# SCH.net
KiCad netlist of a schematic drawn in Altium Designer
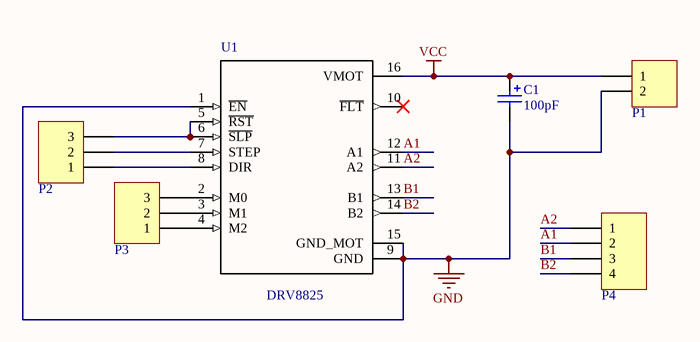
[diagram p0: SCH.SchDoc]

(export (version "E")
  (design (tool "Eeschema 10.0.6"))
  (components
    (comp (ref "C1")
      (value "100pF")
      (footprint "CP1/2")
      (description "Polarized Capacitor (Radial)")
      (fields (field (name "Comment") "Cap Pol"))
      (libsource (lib "PIF_Library") (part "Cap Pol"))
    )
    (comp (ref "P1")
      (value "Domino 2")
      (footprint "DOMINO 2- 5mm")
      (description "Domino, 2-Pin")
      (fields (field (name "PUBLISHER") "Altium Limited"))
      (libsource (lib "PIF_Library") (part "Domino 2"))
    )
    (comp (ref "P2")
      (value "Header 3")
      (footprint "JP3")
      (description "Header, 3-Pin")
      (fields (field (name "PUBLISHER") "Altium Limited"))
      (libsource (lib "PIF_Library") (part "Header 3"))
    )
    (comp (ref "P3")
      (value "Header 3")
      (footprint "JP3")
      (description "Header, 3-Pin")
      (fields (field (name "PUBLISHER") "Altium Limited"))
      (libsource (lib "PIF_Library") (part "Header 3"))
    )
    (comp (ref "P4")
      (value "Header 4")
      (footprint "JP4")
      (description "Header, 4-Pin")
      (fields (field (name "PUBLISHER") "Altium Limited"))
      (libsource (lib "PIF_Library") (part "Header 4"))
    )
    (comp (ref "U1")
      (value "DRV8825")
      (footprint "*IC_DRV8825_STEPPER_MOTOR_DRIVER_CARRIER")
      (description "DRV8825 Motor Controller/Driver Power Management Evaluation Board")
      (fields (field (name "MP") "DRV8825 STEPPER MOTOR DRIVER CARRIER") (field (name "MF") "Pololu"))
      (libsource (lib "DRV8825_STEPPER_MOTOR_DRIVER_CARRIER") (part "DRV8825_STEPPER_MOTOR_DRIVER_CARRIER"))
    )
  )
  (nets
    (net (code "1") (name "/A1") (class "Default")
      (node (ref "P4") (pin "2") (pinfunction "2_2") (pintype "passive"))
      (node (ref "U1") (pin "12") (pinfunction "A1_12") (pintype "output"))
    )
    (net (code "2") (name "/A2") (class "Default")
      (node (ref "P4") (pin "1") (pinfunction "1_1") (pintype "passive"))
      (node (ref "U1") (pin "11") (pinfunction "A2_11") (pintype "output"))
    )
    (net (code "3") (name "/B1") (class "Default")
      (node (ref "P4") (pin "3") (pinfunction "3_3") (pintype "passive"))
      (node (ref "U1") (pin "13") (pinfunction "B1_13") (pintype "output"))
    )
    (net (code "4") (name "/B2") (class "Default")
      (node (ref "P4") (pin "4") (pinfunction "4_4") (pintype "passive"))
      (node (ref "U1") (pin "14") (pinfunction "B2_14") (pintype "output"))
    )
    (net (code "5") (name "GND") (class "Default")
      (node (ref "C1") (pin "2") (pinfunction "2_2") (pintype "passive"))
      (node (ref "P1") (pin "2") (pinfunction "2_2") (pintype "passive"))
      (node (ref "U1") (pin "1") (pinfunction "~{EN}_1") (pintype "input"))
      (node (ref "U1") (pin "15") (pinfunction "GND_MOT_15") (pintype "power_in"))
      (node (ref "U1") (pin "9") (pinfunction "GND_9") (pintype "power_in"))
    )
    (net (code "6") (name "Net-(U1-DIR)") (class "Default")
      (node (ref "P2") (pin "1") (pinfunction "1_1") (pintype "passive"))
      (node (ref "U1") (pin "8") (pinfunction "DIR_8") (pintype "input"))
    )
    (net (code "7") (name "Net-(U1-M0)") (class "Default")
      (node (ref "P3") (pin "3") (pinfunction "3_3") (pintype "passive"))
      (node (ref "U1") (pin "2") (pinfunction "M0_2") (pintype "input"))
    )
    (net (code "8") (name "Net-(U1-M1)") (class "Default")
      (node (ref "P3") (pin "2") (pinfunction "2_2") (pintype "passive"))
      (node (ref "U1") (pin "3") (pinfunction "M1_3") (pintype "input"))
    )
    (net (code "9") (name "Net-(U1-M2)") (class "Default")
      (node (ref "P3") (pin "1") (pinfunction "1_1") (pintype "passive"))
      (node (ref "U1") (pin "4") (pinfunction "M2_4") (pintype "input"))
    )
    (net (code "10") (name "Net-(U1-STEP)") (class "Default")
      (node (ref "P2") (pin "2") (pinfunction "2_2") (pintype "passive"))
      (node (ref "U1") (pin "7") (pinfunction "STEP_7") (pintype "input"))
    )
    (net (code "11") (name "Net-(U1-~{RST})") (class "Default")
      (node (ref "P2") (pin "3") (pinfunction "3_3") (pintype "passive"))
      (node (ref "U1") (pin "5") (pinfunction "~{RST}_5") (pintype "input"))
      (node (ref "U1") (pin "6") (pinfunction "~{SLP}_6") (pintype "input"))
    )
    (net (code "12") (name "VCC") (class "Default")
      (node (ref "C1") (pin "1") (pinfunction "1_1") (pintype "passive"))
      (node (ref "P1") (pin "1") (pinfunction "1_1") (pintype "passive"))
      (node (ref "U1") (pin "16") (pinfunction "VMOT_16") (pintype "power_in"))
    )
    (net (code "13") (name "unconnected-(U1-~{FLT}-Pad10)") (class "Default")
      (node (ref "U1") (pin "10") (pinfunction "~{FLT}_10") (pintype "output+no_connect"))
    )
  )
)
